# rf_bms.net
KiCad netlist of a schematic drawn in Altium Designer
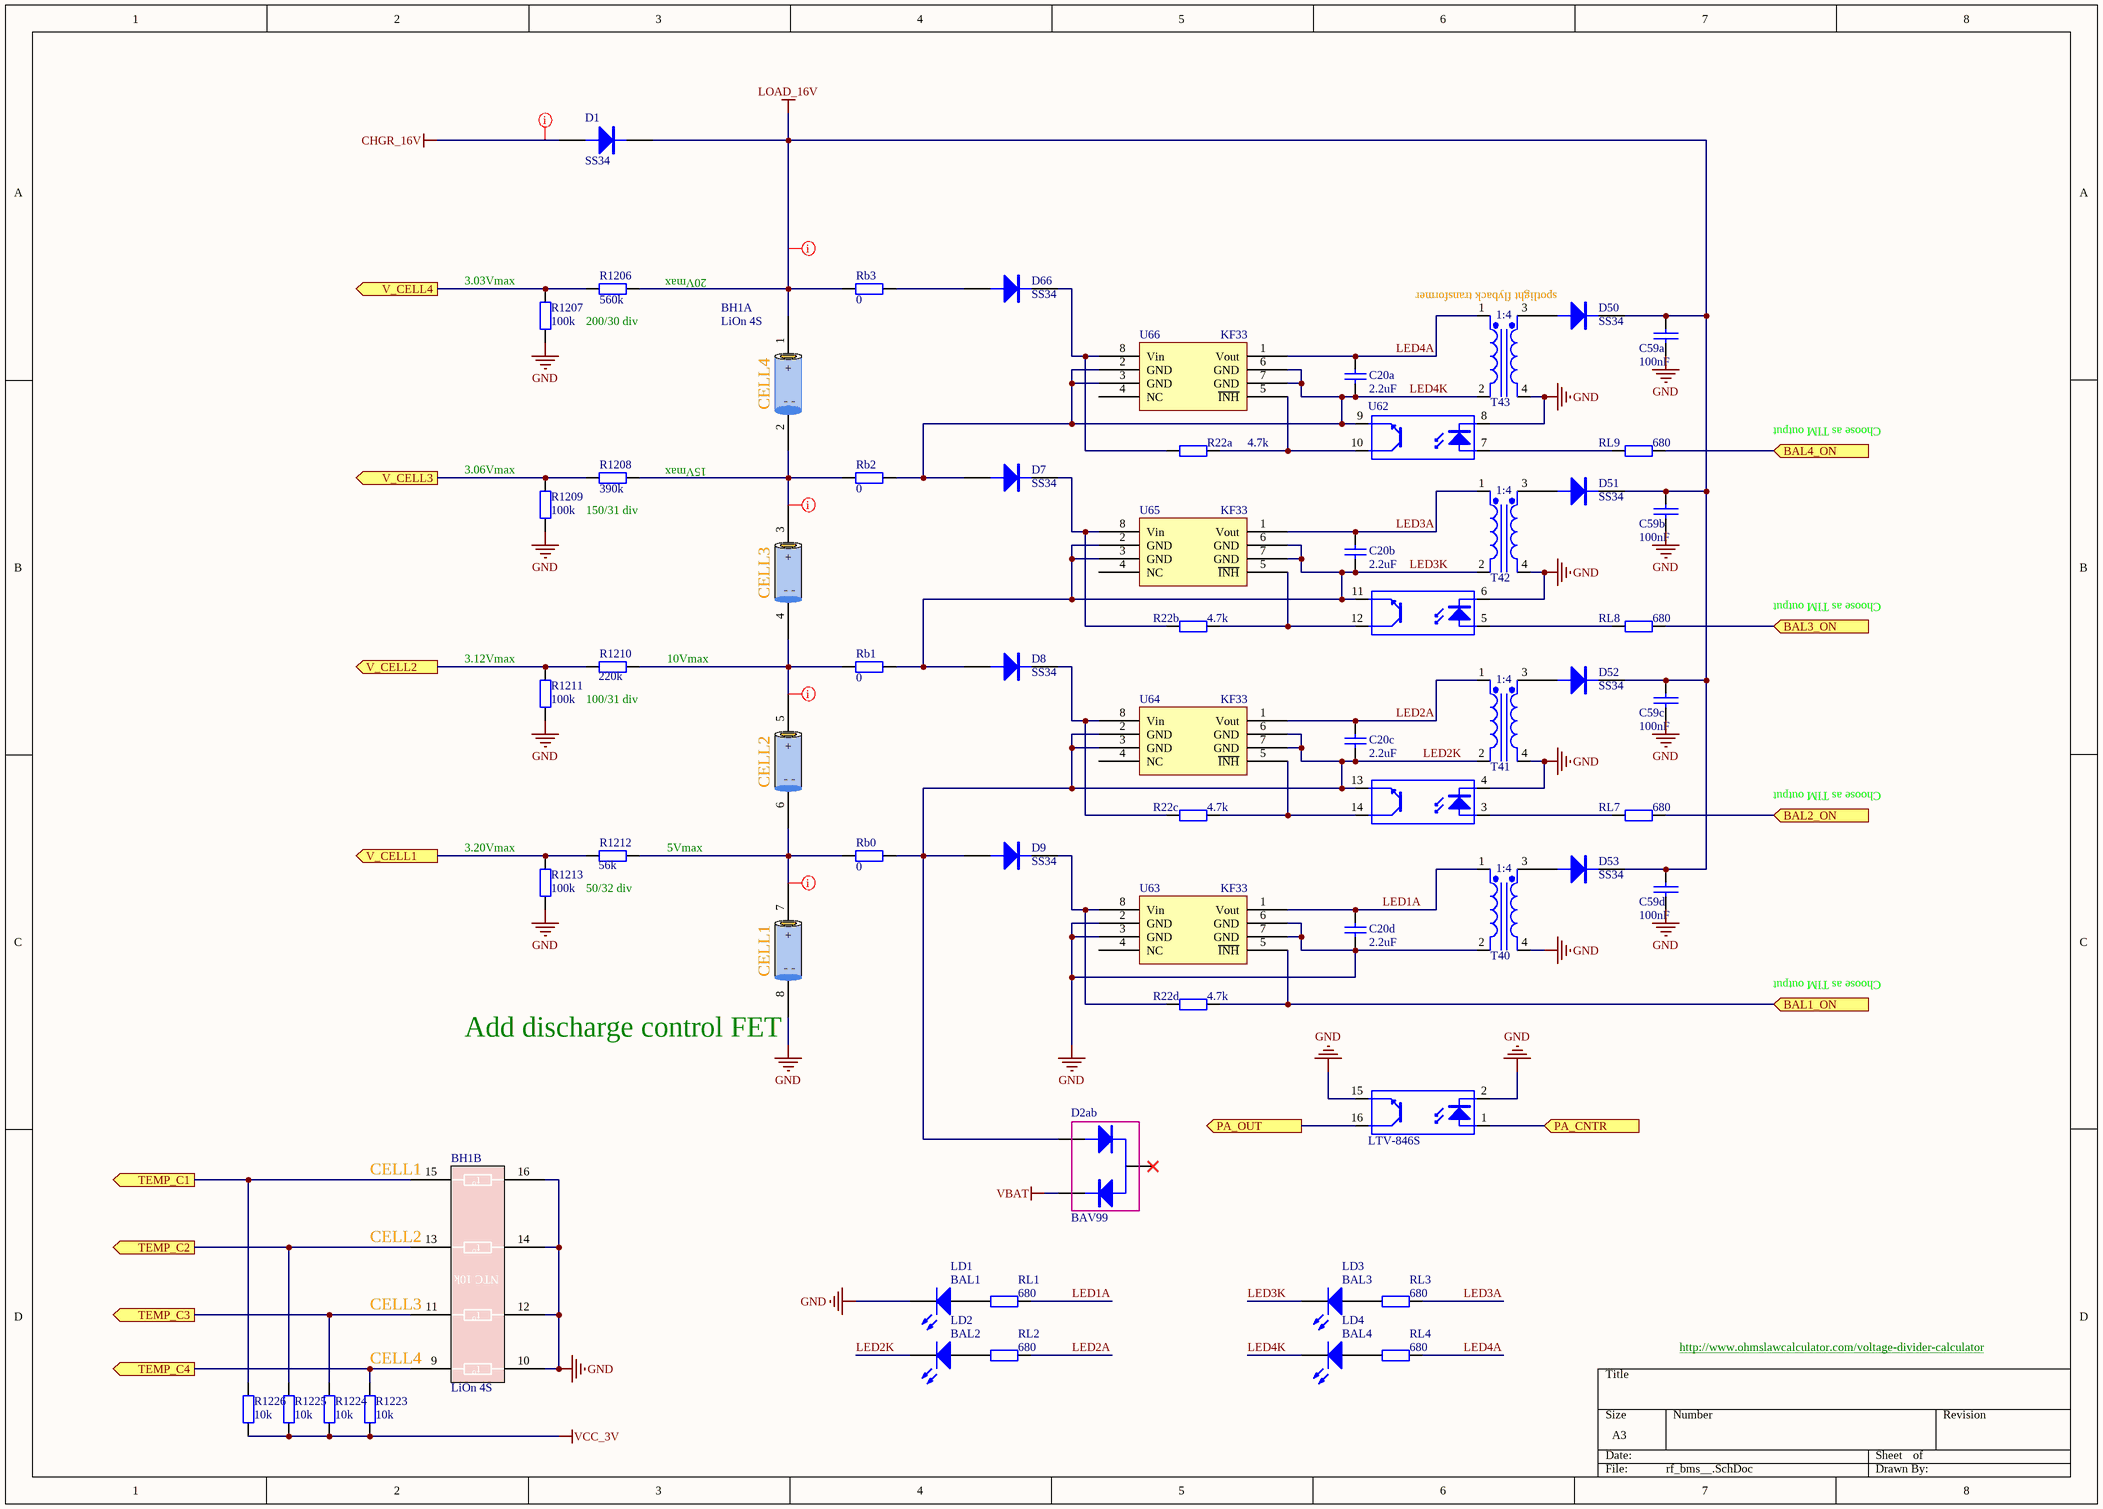
[diagram p0: rf_bms__.SchDoc]

(export (version "E")
  (design (tool "Eeschema 10.0.6"))
  (components
    (comp (ref "BH1")
      (value "LiOn 4S")
      (footprint "BATT_HOLDER")
      (description "LiOn 18650 4S Holder")
      (libsource (lib "mcHF_rf") (part "BATT_HOLDER"))
    )
    (comp (ref "C20a")
      (value "2.2uF")
      (footprint "0805")
      (description "Capacitor")
      (fields (field (name "PUBLISHER") "Altium Limited"))
      (libsource (lib "Miscellaneous Devices") (part "CAP"))
    )
    (comp (ref "C20b")
      (value "2.2uF")
      (footprint "0805")
      (description "Capacitor")
      (fields (field (name "PUBLISHER") "Altium Limited"))
      (libsource (lib "Miscellaneous Devices") (part "CAP"))
    )
    (comp (ref "C20c")
      (value "2.2uF")
      (footprint "0805")
      (description "Capacitor")
      (fields (field (name "PUBLISHER") "Altium Limited"))
      (libsource (lib "Miscellaneous Devices") (part "CAP"))
    )
    (comp (ref "C20d")
      (value "2.2uF")
      (footprint "0805")
      (description "Capacitor")
      (fields (field (name "PUBLISHER") "Altium Limited"))
      (libsource (lib "Miscellaneous Devices") (part "CAP"))
    )
    (comp (ref "C59a")
      (value "100nF")
      (footprint "0805")
      (description "Capacitor")
      (fields (field (name "VOLTAGE") "100V"))
      (libsource (lib "mcHF_rf") (part "CAP"))
    )
    (comp (ref "C59b")
      (value "100nF")
      (footprint "0805")
      (description "Capacitor")
      (fields (field (name "VOLTAGE") "100V"))
      (libsource (lib "mcHF_rf") (part "CAP"))
    )
    (comp (ref "C59c")
      (value "100nF")
      (footprint "0805")
      (description "Capacitor")
      (fields (field (name "VOLTAGE") "100V"))
      (libsource (lib "mcHF_rf") (part "CAP"))
    )
    (comp (ref "C59d")
      (value "100nF")
      (footprint "0805")
      (description "Capacitor")
      (fields (field (name "VOLTAGE") "100V"))
      (libsource (lib "mcHF_rf") (part "CAP"))
    )
    (comp (ref "D1")
      (value "SS34")
      (footprint "SOD87")
      (description "DIODE, SCHOTTKY, 1A, 60V, SOD-123F")
      (libsource (lib "mcHF_rf") (part "PMEG6010CEH"))
    )
    (comp (ref "D2ab")
      (value "BAV99")
      (footprint "SOT-23")
      (description "Small Signal Diode, Dual Series")
      (libsource (lib "mcHF_rf") (part "BAV99"))
    )
    (comp (ref "D7")
      (value "SS34")
      (footprint "SOD87")
      (description "DIODE, SCHOTTKY, 1A, 60V, SOD-123F")
      (libsource (lib "mcHF_rf") (part "PMEG6010CEH"))
    )
    (comp (ref "D8")
      (value "SS34")
      (footprint "SOD87")
      (description "DIODE, SCHOTTKY, 1A, 60V, SOD-123F")
      (libsource (lib "mcHF_rf") (part "PMEG6010CEH"))
    )
    (comp (ref "D9")
      (value "SS34")
      (footprint "SOD87")
      (description "DIODE, SCHOTTKY, 1A, 60V, SOD-123F")
      (libsource (lib "mcHF_rf") (part "PMEG6010CEH"))
    )
    (comp (ref "D50")
      (value "SS34")
      (footprint "SOD87")
      (description "DIODE, SCHOTTKY, 1A, 60V, SOD-123F")
      (libsource (lib "mcHF_rf") (part "PMEG6010CEH"))
    )
    (comp (ref "D51")
      (value "SS34")
      (footprint "SOD87")
      (description "DIODE, SCHOTTKY, 1A, 60V, SOD-123F")
      (libsource (lib "mcHF_rf") (part "PMEG6010CEH"))
    )
    (comp (ref "D52")
      (value "SS34")
      (footprint "SOD87")
      (description "DIODE, SCHOTTKY, 1A, 60V, SOD-123F")
      (libsource (lib "mcHF_rf") (part "PMEG6010CEH"))
    )
    (comp (ref "D53")
      (value "SS34")
      (footprint "SOD87")
      (description "DIODE, SCHOTTKY, 1A, 60V, SOD-123F")
      (libsource (lib "mcHF_rf") (part "PMEG6010CEH"))
    )
    (comp (ref "D66")
      (value "SS34")
      (footprint "SOD87")
      (description "DIODE, SCHOTTKY, 1A, 60V, SOD-123F")
      (libsource (lib "mcHF_rf") (part "PMEG6010CEH"))
    )
    (comp (ref "LD1")
      (value "BAL1")
      (footprint "0805_led")
      (description "LED 3mm")
      (libsource (lib "mcHF_ui") (part "LED2"))
    )
    (comp (ref "LD2")
      (value "BAL2")
      (footprint "0805_led")
      (description "LED 3mm")
      (libsource (lib "mcHF_ui") (part "LED2"))
    )
    (comp (ref "LD3")
      (value "BAL3")
      (footprint "0805_led")
      (description "LED 3mm")
      (libsource (lib "mcHF_ui") (part "LED2"))
    )
    (comp (ref "LD4")
      (value "BAL4")
      (footprint "0805_led")
      (description "LED 3mm")
      (libsource (lib "mcHF_ui") (part "LED2"))
    )
    (comp (ref "R22a")
      (value "4.7k")
      (footprint "0805")
      (description "Resistor")
      (libsource (lib "mcHF_rf") (part "RES"))
    )
    (comp (ref "R22b")
      (value "4.7k")
      (footprint "0805")
      (description "Resistor")
      (libsource (lib "mcHF_rf") (part "RES"))
    )
    (comp (ref "R22c")
      (value "4.7k")
      (footprint "0805")
      (description "Resistor")
      (libsource (lib "mcHF_rf") (part "RES"))
    )
    (comp (ref "R22d")
      (value "4.7k")
      (footprint "0805")
      (description "Resistor")
      (libsource (lib "mcHF_rf") (part "RES"))
    )
    (comp (ref "R1206")
      (value "560k")
      (footprint "0805")
      (description "Resistor")
      (libsource (lib "mcHF_rf") (part "RES"))
    )
    (comp (ref "R1207")
      (value "100k")
      (footprint "0805")
      (description "Resistor")
      (libsource (lib "") (part "RES_1"))
    )
    (comp (ref "R1208")
      (value "390k")
      (footprint "0805")
      (description "Resistor")
      (libsource (lib "") (part "RES_2"))
    )
    (comp (ref "R1209")
      (value "100k")
      (footprint "0805")
      (description "Resistor")
      (libsource (lib "") (part "RES_1"))
    )
    (comp (ref "R1210")
      (value "220k")
      (footprint "0805")
      (description "Resistor")
      (libsource (lib "mcHF_rf") (part "RES"))
    )
    (comp (ref "R1211")
      (value "100k")
      (footprint "0805")
      (description "Resistor")
      (libsource (lib "") (part "RES_1"))
    )
    (comp (ref "R1212")
      (value "56k")
      (footprint "0805")
      (description "Resistor")
      (libsource (lib "mcHF_rf") (part "RES"))
    )
    (comp (ref "R1213")
      (value "100k")
      (footprint "0805")
      (description "Resistor")
      (libsource (lib "") (part "RES_1"))
    )
    (comp (ref "R1223")
      (value "10k")
      (footprint "0805")
      (description "Resistor")
      (libsource (lib "") (part "RES_3"))
    )
    (comp (ref "R1224")
      (value "10k")
      (footprint "0805")
      (description "Resistor")
      (libsource (lib "") (part "RES_3"))
    )
    (comp (ref "R1225")
      (value "10k")
      (footprint "0805")
      (description "Resistor")
      (libsource (lib "") (part "RES_3"))
    )
    (comp (ref "R1226")
      (value "10k")
      (footprint "0805")
      (description "Resistor")
      (libsource (lib "") (part "RES_3"))
    )
    (comp (ref "Rb0")
      (value "0")
      (footprint "0805")
      (description "Resistor")
      (libsource (lib "mcHF_rf") (part "RES"))
    )
    (comp (ref "Rb1")
      (value "0")
      (footprint "0805")
      (description "Resistor")
      (libsource (lib "mcHF_rf") (part "RES"))
    )
    (comp (ref "Rb2")
      (value "0")
      (footprint "0805")
      (description "Resistor")
      (libsource (lib "mcHF_rf") (part "RES"))
    )
    (comp (ref "Rb3")
      (value "0")
      (footprint "0805")
      (description "Resistor")
      (libsource (lib "mcHF_rf") (part "RES"))
    )
    (comp (ref "RL1")
      (value "680")
      (footprint "0805")
      (description "Resistor")
      (libsource (lib "mcHF_ui_b") (part "RES"))
    )
    (comp (ref "RL2")
      (value "680")
      (footprint "0805")
      (description "Resistor")
      (libsource (lib "mcHF_ui_b") (part "RES"))
    )
    (comp (ref "RL3")
      (value "680")
      (footprint "0805")
      (description "Resistor")
      (libsource (lib "mcHF_ui_b") (part "RES"))
    )
    (comp (ref "RL4")
      (value "680")
      (footprint "0805")
      (description "Resistor")
      (libsource (lib "mcHF_ui_b") (part "RES"))
    )
    (comp (ref "RL7")
      (value "680")
      (footprint "0805")
      (description "Resistor")
      (libsource (lib "mcHF_ui_b") (part "RES"))
    )
    (comp (ref "RL8")
      (value "680")
      (footprint "0805")
      (description "Resistor")
      (libsource (lib "mcHF_ui_b") (part "RES"))
    )
    (comp (ref "RL9")
      (value "680")
      (footprint "0805")
      (description "Resistor")
      (libsource (lib "mcHF_ui_b") (part "RES"))
    )
    (comp (ref "T40")
      (value "1:4")
      (footprint "FB_TR")
      (description "Flyback transformer 1:4")
      (libsource (lib "__rf") (part "FB_TR"))
    )
    (comp (ref "T41")
      (value "1:4")
      (footprint "FB_TR")
      (description "Flyback transformer 1:4")
      (libsource (lib "__rf") (part "FB_TR"))
    )
    (comp (ref "T42")
      (value "1:4")
      (footprint "FB_TR")
      (description "Flyback transformer 1:4")
      (libsource (lib "__rf") (part "FB_TR"))
    )
    (comp (ref "T43")
      (value "1:4")
      (footprint "FB_TR")
      (description "Flyback transformer 1:4")
      (libsource (lib "__rf") (part "FB_TR"))
    )
    (comp (ref "U62")
      (value "LTV-846S")
      (footprint "SMDIP-8")
      (description "Quad Opto Coupler")
      (libsource (lib "__rf") (part "QUAD_OPTO"))
    )
    (comp (ref "U63")
      (value "KF33")
      (footprint "SO-8")
      (description "5V regulator with inhibit")
      (libsource (lib "mcHF_rf") (part "KF50"))
    )
    (comp (ref "U64")
      (value "KF33")
      (footprint "SO-8")
      (description "5V regulator with inhibit")
      (libsource (lib "mcHF_rf") (part "KF50"))
    )
    (comp (ref "U65")
      (value "KF33")
      (footprint "SO-8")
      (description "5V regulator with inhibit")
      (libsource (lib "mcHF_rf") (part "KF50"))
    )
    (comp (ref "U66")
      (value "KF33")
      (footprint "SO-8")
      (description "5V regulator with inhibit")
      (libsource (lib "mcHF_rf") (part "KF50"))
    )
  )
  (nets
    (net (code "1") (name "/BAL1_ON") (class "Default")
      (node (ref "R22d") (pin "1") (pinfunction "1_1") (pintype "passive"))
      (node (ref "U63") (pin "5") (pinfunction "~{INH}_5") (pintype "passive"))
    )
    (net (code "2") (name "/BAL2_ON") (class "Default")
      (node (ref "RL7") (pin "1") (pinfunction "1_1") (pintype "passive"))
    )
    (net (code "3") (name "/BAL3_ON") (class "Default")
      (node (ref "RL8") (pin "1") (pinfunction "1_1") (pintype "passive"))
    )
    (net (code "4") (name "/BAL4_ON") (class "Default")
      (node (ref "RL9") (pin "1") (pinfunction "1_1") (pintype "passive"))
    )
    (net (code "5") (name "/LED1A") (class "Default")
      (node (ref "C20d") (pin "2") (pinfunction "2_2") (pintype "passive"))
      (node (ref "RL1") (pin "1") (pinfunction "1_1") (pintype "passive"))
      (node (ref "T40") (pin "1") (pinfunction "Pri+_1") (pintype "passive"))
      (node (ref "U63") (pin "1") (pinfunction "Vout_1") (pintype "passive"))
    )
    (net (code "6") (name "/LED2A") (class "Default")
      (node (ref "C20c") (pin "2") (pinfunction "2_2") (pintype "passive"))
      (node (ref "RL2") (pin "1") (pinfunction "1_1") (pintype "passive"))
      (node (ref "T41") (pin "1") (pinfunction "Pri+_1") (pintype "passive"))
      (node (ref "U64") (pin "1") (pinfunction "Vout_1") (pintype "passive"))
    )
    (net (code "7") (name "/LED2K") (class "Default")
      (node (ref "C20c") (pin "1") (pinfunction "1_1") (pintype "passive"))
      (node (ref "D2ab") (pin "1") (pinfunction "A1_1") (pintype "passive"))
      (node (ref "D9") (pin "1") (pinfunction "A_1") (pintype "passive"))
      (node (ref "LD2") (pin "2") (pinfunction "K_2") (pintype "passive"))
      (node (ref "Rb0") (pin "1") (pinfunction "1_1") (pintype "passive"))
      (node (ref "T41") (pin "2") (pinfunction "Pri-_2") (pintype "passive"))
      (node (ref "U62") (pin "13") (pinfunction "E_13") (pintype "passive"))
      (node (ref "U64") (pin "2") (pinfunction "GND_2") (pintype "passive"))
      (node (ref "U64") (pin "3") (pinfunction "GND_3") (pintype "passive"))
      (node (ref "U64") (pin "6") (pinfunction "GND_6") (pintype "passive"))
      (node (ref "U64") (pin "7") (pinfunction "GND_7") (pintype "passive"))
    )
    (net (code "8") (name "/LED3A") (class "Default")
      (node (ref "C20b") (pin "2") (pinfunction "2_2") (pintype "passive"))
      (node (ref "RL3") (pin "1") (pinfunction "1_1") (pintype "passive"))
      (node (ref "T42") (pin "1") (pinfunction "Pri+_1") (pintype "passive"))
      (node (ref "U65") (pin "1") (pinfunction "Vout_1") (pintype "passive"))
    )
    (net (code "9") (name "/LED3K") (class "Default")
      (node (ref "C20b") (pin "1") (pinfunction "1_1") (pintype "passive"))
      (node (ref "D8") (pin "1") (pinfunction "A_1") (pintype "passive"))
      (node (ref "LD3") (pin "2") (pinfunction "K_2") (pintype "passive"))
      (node (ref "Rb1") (pin "1") (pinfunction "1_1") (pintype "passive"))
      (node (ref "T42") (pin "2") (pinfunction "Pri-_2") (pintype "passive"))
      (node (ref "U62") (pin "11") (pinfunction "E_11") (pintype "passive"))
      (node (ref "U65") (pin "2") (pinfunction "GND_2") (pintype "passive"))
      (node (ref "U65") (pin "3") (pinfunction "GND_3") (pintype "passive"))
      (node (ref "U65") (pin "6") (pinfunction "GND_6") (pintype "passive"))
      (node (ref "U65") (pin "7") (pinfunction "GND_7") (pintype "passive"))
    )
    (net (code "10") (name "/LED4A") (class "Default")
      (node (ref "C20a") (pin "2") (pinfunction "2_2") (pintype "passive"))
      (node (ref "RL4") (pin "1") (pinfunction "1_1") (pintype "passive"))
      (node (ref "T43") (pin "1") (pinfunction "Pri+_1") (pintype "passive"))
      (node (ref "U66") (pin "1") (pinfunction "Vout_1") (pintype "passive"))
    )
    (net (code "11") (name "/LED4K") (class "Default")
      (node (ref "C20a") (pin "1") (pinfunction "1_1") (pintype "passive"))
      (node (ref "D7") (pin "1") (pinfunction "A_1") (pintype "passive"))
      (node (ref "LD4") (pin "2") (pinfunction "K_2") (pintype "passive"))
      (node (ref "Rb2") (pin "1") (pinfunction "1_1") (pintype "passive"))
      (node (ref "T43") (pin "2") (pinfunction "Pri-_2") (pintype "passive"))
      (node (ref "U62") (pin "9") (pinfunction "E_9") (pintype "passive"))
      (node (ref "U66") (pin "2") (pinfunction "GND_2") (pintype "passive"))
      (node (ref "U66") (pin "3") (pinfunction "GND_3") (pintype "passive"))
      (node (ref "U66") (pin "6") (pinfunction "GND_6") (pintype "passive"))
      (node (ref "U66") (pin "7") (pinfunction "GND_7") (pintype "passive"))
    )
    (net (code "12") (name "/PA_CNTR") (class "Default")
      (node (ref "U62") (pin "1") (pinfunction "A_1") (pintype "passive"))
    )
    (net (code "13") (name "/PA_OUT") (class "Default")
      (node (ref "U62") (pin "16") (pinfunction "C_16") (pintype "passive"))
    )
    (net (code "14") (name "/TEMP_C1") (class "Default")
      (node (ref "BH1") (pin "15") (pintype "passive"))
      (node (ref "R1226") (pin "2") (pinfunction "2_2") (pintype "passive"))
    )
    (net (code "15") (name "/TEMP_C2") (class "Default")
      (node (ref "BH1") (pin "13") (pintype "passive"))
      (node (ref "R1225") (pin "2") (pinfunction "2_2") (pintype "passive"))
    )
    (net (code "16") (name "/TEMP_C3") (class "Default")
      (node (ref "BH1") (pin "11") (pintype "passive"))
      (node (ref "R1224") (pin "2") (pinfunction "2_2") (pintype "passive"))
    )
    (net (code "17") (name "/TEMP_C4") (class "Default")
      (node (ref "BH1") (pin "9") (pintype "passive"))
      (node (ref "R1223") (pin "2") (pinfunction "2_2") (pintype "passive"))
    )
    (net (code "18") (name "/V_CELL1") (class "Default")
      (node (ref "R1212") (pin "2") (pinfunction "2_2") (pintype "passive"))
      (node (ref "R1213") (pin "1") (pinfunction "1_1") (pintype "passive"))
    )
    (net (code "19") (name "/V_CELL2") (class "Default")
      (node (ref "R1210") (pin "2") (pinfunction "2_2") (pintype "passive"))
      (node (ref "R1211") (pin "1") (pinfunction "1_1") (pintype "passive"))
    )
    (net (code "20") (name "/V_CELL3") (class "Default")
      (node (ref "R1208") (pin "1") (pinfunction "1_1") (pintype "passive"))
      (node (ref "R1209") (pin "1") (pinfunction "1_1") (pintype "passive"))
    )
    (net (code "21") (name "/V_CELL4") (class "Default")
      (node (ref "R1206") (pin "2") (pinfunction "2_2") (pintype "passive"))
      (node (ref "R1207") (pin "1") (pinfunction "1_1") (pintype "passive"))
    )
    (net (code "22") (name "CHGR_16V") (class "Default")
      (node (ref "D1") (pin "1") (pinfunction "A_1") (pintype "passive"))
    )
    (net (code "23") (name "GND") (class "Default")
      (node (ref "BH1") (pin "10") (pintype "passive"))
      (node (ref "BH1") (pin "12") (pintype "passive"))
      (node (ref "BH1") (pin "14") (pintype "passive"))
      (node (ref "BH1") (pin "16") (pintype "passive"))
      (node (ref "BH1") (pin "8") (pinfunction "¦_8") (pintype "passive"))
      (node (ref "C20d") (pin "1") (pinfunction "1_1") (pintype "passive"))
      (node (ref "C59a") (pin "2") (pinfunction "2_2") (pintype "passive"))
      (node (ref "C59b") (pin "2") (pinfunction "2_2") (pintype "passive"))
      (node (ref "C59c") (pin "2") (pinfunction "2_2") (pintype "passive"))
      (node (ref "C59d") (pin "2") (pinfunction "2_2") (pintype "passive"))
      (node (ref "LD1") (pin "2") (pinfunction "K_2") (pintype "passive"))
      (node (ref "R1207") (pin "2") (pinfunction "2_2") (pintype "passive"))
      (node (ref "R1209") (pin "2") (pinfunction "2_2") (pintype "passive"))
      (node (ref "R1211") (pin "2") (pinfunction "2_2") (pintype "passive"))
      (node (ref "R1213") (pin "2") (pinfunction "2_2") (pintype "passive"))
      (node (ref "T40") (pin "2") (pinfunction "Pri-_2") (pintype "passive"))
      (node (ref "T40") (pin "4") (pinfunction "Sec-_4") (pintype "passive"))
      (node (ref "T41") (pin "4") (pinfunction "Sec-_4") (pintype "passive"))
      (node (ref "T42") (pin "4") (pinfunction "Sec-_4") (pintype "passive"))
      (node (ref "T43") (pin "4") (pinfunction "Sec-_4") (pintype "passive"))
      (node (ref "U62") (pin "15") (pinfunction "E_15") (pintype "passive"))
      (node (ref "U62") (pin "2") (pinfunction "K_2") (pintype "passive"))
      (node (ref "U62") (pin "4") (pinfunction "K_4") (pintype "passive"))
      (node (ref "U62") (pin "6") (pinfunction "K_6") (pintype "passive"))
      (node (ref "U62") (pin "8") (pinfunction "K_8") (pintype "passive"))
      (node (ref "U63") (pin "2") (pinfunction "GND_2") (pintype "passive"))
      (node (ref "U63") (pin "3") (pinfunction "GND_3") (pintype "passive"))
      (node (ref "U63") (pin "6") (pinfunction "GND_6") (pintype "passive"))
      (node (ref "U63") (pin "7") (pinfunction "GND_7") (pintype "passive"))
    )
    (net (code "24") (name "LOAD_16V") (class "Default")
      (node (ref "BH1") (pin "1") (pinfunction "+_1") (pintype "passive"))
      (node (ref "C59a") (pin "1") (pinfunction "1_1") (pintype "passive"))
      (node (ref "C59b") (pin "1") (pinfunction "1_1") (pintype "passive"))
      (node (ref "C59c") (pin "1") (pinfunction "1_1") (pintype "passive"))
      (node (ref "C59d") (pin "1") (pinfunction "1_1") (pintype "passive"))
      (node (ref "D1") (pin "2") (pinfunction "K_2") (pintype "passive"))
      (node (ref "D50") (pin "2") (pinfunction "K_2") (pintype "passive"))
      (node (ref "D51") (pin "2") (pinfunction "K_2") (pintype "passive"))
      (node (ref "D52") (pin "2") (pinfunction "K_2") (pintype "passive"))
      (node (ref "D53") (pin "2") (pinfunction "K_2") (pintype "passive"))
      (node (ref "R1206") (pin "1") (pinfunction "1_1") (pintype "passive"))
      (node (ref "Rb3") (pin "2") (pinfunction "2_2") (pintype "passive"))
    )
    (net (code "25") (name "Net-(BH1A-+-Pad3)") (class "Default")
      (node (ref "BH1") (pin "2") (pinfunction "¦_2") (pintype "passive"))
      (node (ref "BH1") (pin "3") (pinfunction "+_3") (pintype "passive"))
      (node (ref "R1208") (pin "2") (pinfunction "2_2") (pintype "passive"))
      (node (ref "Rb2") (pin "2") (pinfunction "2_2") (pintype "passive"))
    )
    (net (code "26") (name "Net-(BH1A-+-Pad5)") (class "Default")
      (node (ref "BH1") (pin "4") (pinfunction "¦_4") (pintype "passive"))
      (node (ref "BH1") (pin "5") (pinfunction "+_5") (pintype "passive"))
      (node (ref "R1210") (pin "1") (pinfunction "1_1") (pintype "passive"))
      (node (ref "Rb1") (pin "2") (pinfunction "2_2") (pintype "passive"))
    )
    (net (code "27") (name "Net-(BH1A-+-Pad7)") (class "Default")
      (node (ref "BH1") (pin "6") (pinfunction "¦_6") (pintype "passive"))
      (node (ref "BH1") (pin "7") (pinfunction "+_7") (pintype "passive"))
      (node (ref "R1212") (pin "1") (pinfunction "1_1") (pintype "passive"))
      (node (ref "Rb0") (pin "2") (pinfunction "2_2") (pintype "passive"))
    )
    (net (code "28") (name "Net-(D7-K)") (class "Default")
      (node (ref "D7") (pin "2") (pinfunction "K_2") (pintype "passive"))
      (node (ref "R22b") (pin "2") (pinfunction "2_2") (pintype "passive"))
      (node (ref "U65") (pin "8") (pinfunction "Vin_8") (pintype "passive"))
    )
    (net (code "29") (name "Net-(D8-K)") (class "Default")
      (node (ref "D8") (pin "2") (pinfunction "K_2") (pintype "passive"))
      (node (ref "R22c") (pin "2") (pinfunction "2_2") (pintype "passive"))
      (node (ref "U64") (pin "8") (pinfunction "Vin_8") (pintype "passive"))
    )
    (net (code "30") (name "Net-(D9-K)") (class "Default")
      (node (ref "D9") (pin "2") (pinfunction "K_2") (pintype "passive"))
      (node (ref "R22d") (pin "2") (pinfunction "2_2") (pintype "passive"))
      (node (ref "U63") (pin "8") (pinfunction "Vin_8") (pintype "passive"))
    )
    (net (code "31") (name "Net-(D50-A)") (class "Default")
      (node (ref "D50") (pin "1") (pinfunction "A_1") (pintype "passive"))
      (node (ref "T43") (pin "3") (pinfunction "Sec+_3") (pintype "passive"))
    )
    (net (code "32") (name "Net-(D51-A)") (class "Default")
      (node (ref "D51") (pin "1") (pinfunction "A_1") (pintype "passive"))
      (node (ref "T42") (pin "3") (pinfunction "Sec+_3") (pintype "passive"))
    )
    (net (code "33") (name "Net-(D52-A)") (class "Default")
      (node (ref "D52") (pin "1") (pinfunction "A_1") (pintype "passive"))
      (node (ref "T41") (pin "3") (pinfunction "Sec+_3") (pintype "passive"))
    )
    (net (code "34") (name "Net-(D53-A)") (class "Default")
      (node (ref "D53") (pin "1") (pinfunction "A_1") (pintype "passive"))
      (node (ref "T40") (pin "3") (pinfunction "Sec+_3") (pintype "passive"))
    )
    (net (code "35") (name "Net-(D66-A)") (class "Default")
      (node (ref "D66") (pin "1") (pinfunction "A_1") (pintype "passive"))
      (node (ref "Rb3") (pin "1") (pinfunction "1_1") (pintype "passive"))
    )
    (net (code "36") (name "Net-(D66-K)") (class "Default")
      (node (ref "D66") (pin "2") (pinfunction "K_2") (pintype "passive"))
      (node (ref "R22a") (pin "2") (pinfunction "2_2") (pintype "passive"))
      (node (ref "U66") (pin "8") (pinfunction "Vin_8") (pintype "passive"))
    )
    (net (code "37") (name "Net-(LD1-A)") (class "Default")
      (node (ref "LD1") (pin "1") (pinfunction "A_1") (pintype "passive"))
      (node (ref "RL1") (pin "2") (pinfunction "2_2") (pintype "passive"))
    )
    (net (code "38") (name "Net-(LD2-A)") (class "Default")
      (node (ref "LD2") (pin "1") (pinfunction "A_1") (pintype "passive"))
      (node (ref "RL2") (pin "2") (pinfunction "2_2") (pintype "passive"))
    )
    (net (code "39") (name "Net-(LD3-A)") (class "Default")
      (node (ref "LD3") (pin "1") (pinfunction "A_1") (pintype "passive"))
      (node (ref "RL3") (pin "2") (pinfunction "2_2") (pintype "passive"))
    )
    (net (code "40") (name "Net-(LD4-A)") (class "Default")
      (node (ref "LD4") (pin "1") (pinfunction "A_1") (pintype "passive"))
      (node (ref "RL4") (pin "2") (pinfunction "2_2") (pintype "passive"))
    )
    (net (code "41") (name "Net-(RL7-Pad2)") (class "Default")
      (node (ref "RL7") (pin "2") (pinfunction "2_2") (pintype "passive"))
      (node (ref "U62") (pin "3") (pinfunction "A_3") (pintype "passive"))
    )
    (net (code "42") (name "Net-(RL8-Pad2)") (class "Default")
      (node (ref "RL8") (pin "2") (pinfunction "2_2") (pintype "passive"))
      (node (ref "U62") (pin "5") (pinfunction "A_5") (pintype "passive"))
    )
    (net (code "43") (name "Net-(RL9-Pad2)") (class "Default")
      (node (ref "RL9") (pin "2") (pinfunction "2_2") (pintype "passive"))
      (node (ref "U62") (pin "7") (pinfunction "A_7") (pintype "passive"))
    )
    (net (code "44") (name "Net-(U64-~{INH})") (class "Default")
      (node (ref "R22c") (pin "1") (pinfunction "1_1") (pintype "passive"))
      (node (ref "U62") (pin "14") (pinfunction "C_14") (pintype "passive"))
      (node (ref "U64") (pin "5") (pinfunction "~{INH}_5") (pintype "passive"))
    )
    (net (code "45") (name "Net-(U65-~{INH})") (class "Default")
      (node (ref "R22b") (pin "1") (pinfunction "1_1") (pintype "passive"))
      (node (ref "U62") (pin "12") (pinfunction "C_12") (pintype "passive"))
      (node (ref "U65") (pin "5") (pinfunction "~{INH}_5") (pintype "passive"))
    )
    (net (code "46") (name "Net-(U66-~{INH})") (class "Default")
      (node (ref "R22a") (pin "1") (pinfunction "1_1") (pintype "passive"))
      (node (ref "U62") (pin "10") (pinfunction "C_10") (pintype "passive"))
      (node (ref "U66") (pin "5") (pinfunction "~{INH}_5") (pintype "passive"))
    )
    (net (code "47") (name "VBAT") (class "Default")
      (node (ref "D2ab") (pin "2") (pinfunction "K1_2") (pintype "passive"))
    )
    (net (code "48") (name "VCC_3V") (class "Default")
      (node (ref "R1223") (pin "1") (pinfunction "1_1") (pintype "passive"))
      (node (ref "R1224") (pin "1") (pinfunction "1_1") (pintype "passive"))
      (node (ref "R1225") (pin "1") (pinfunction "1_1") (pintype "passive"))
      (node (ref "R1226") (pin "1") (pinfunction "1_1") (pintype "passive"))
    )
    (net (code "49") (name "unconnected-(D2ab-C-Pad3)") (class "Default")
      (node (ref "D2ab") (pin "3") (pinfunction "C_3") (pintype "passive+no_connect"))
    )
    (net (code "50") (name "unconnected-(U63-NC-Pad4)") (class "Default")
      (node (ref "U63") (pin "4") (pinfunction "NC_4") (pintype "passive"))
    )
    (net (code "51") (name "unconnected-(U64-NC-Pad4)") (class "Default")
      (node (ref "U64") (pin "4") (pinfunction "NC_4") (pintype "passive"))
    )
    (net (code "52") (name "unconnected-(U65-NC-Pad4)") (class "Default")
      (node (ref "U65") (pin "4") (pinfunction "NC_4") (pintype "passive"))
    )
    (net (code "53") (name "unconnected-(U66-NC-Pad4)") (class "Default")
      (node (ref "U66") (pin "4") (pinfunction "NC_4") (pintype "passive"))
    )
  )
)
